# Sheet2.net
KiCad netlist of a schematic drawn in Altium Designer
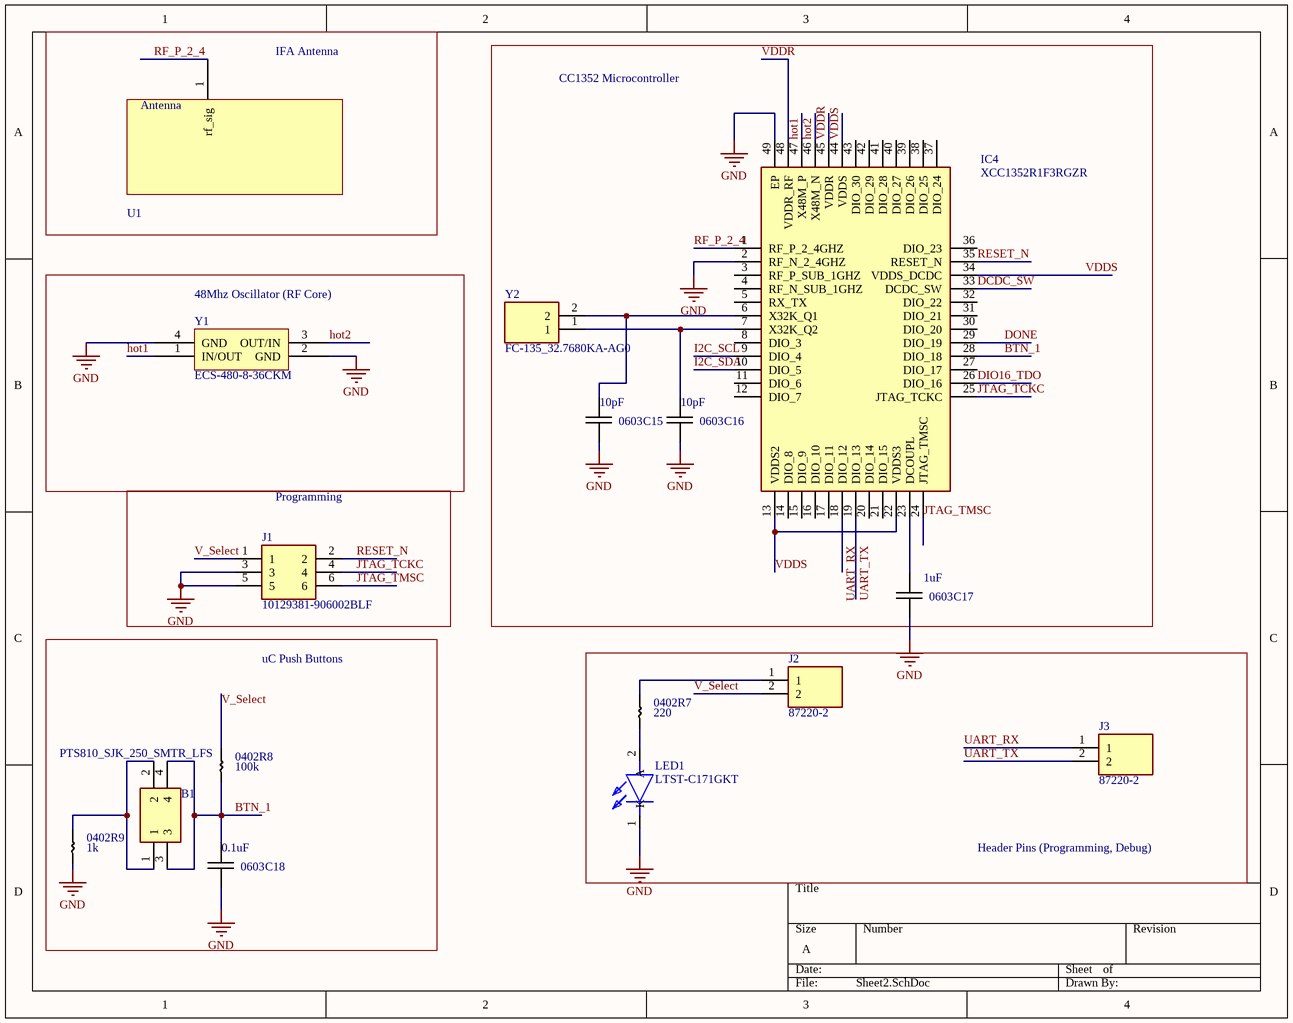
[diagram p0: Sheet2.SchDoc]

(export (version "E")
  (design (tool "Eeschema 10.0.6"))
  (components
    (comp (ref "B1")
      (value "PTS810_SJK_250_SMTR_LFS")
      (footprint "SamacSys:PTS810SJK250SMTRLFS")
      (description "Crystal or Oscillator")
      (fields
        (field (name "MANUFACTURER_PART_NUMBER") "PTS810 SJK 250 SMTR LFS")
        (field (name "MOUSER PART NUMBER") "611-PTS810SJK250SMTR")
      )
      (libsource (lib "*") (part "PTS810_SJK_250_SMTR_LFS"))
    )
    (comp (ref "C15")
      (value "10pF")
      (footprint "0603_SMD")
      (libsource (lib "Enviornmental_Sensor") (part "C_0603"))
    )
    (comp (ref "C16")
      (value "10pF")
      (footprint "0603_SMD")
      (libsource (lib "Enviornmental_Sensor") (part "C_0603"))
    )
    (comp (ref "C17")
      (value "1uF")
      (footprint "0603_SMD")
      (libsource (lib "Enviornmental_Sensor") (part "C_0603"))
    )
    (comp (ref "C18")
      (value "0.1uF")
      (footprint "0603_SMD")
      (libsource (lib "Enviornmental_Sensor") (part "C_0603"))
    )
    (comp (ref "IC4")
      (value "XCC1352R1F3RGZR")
      (footprint "SamacSys:QFN50P700X700X100-49N-D")
      (description "Integrated Circuit")
      (libsource (lib "*") (part "XCC1352R1F3RGZR"))
    )
    (comp (ref "J1")
      (value "10129381-906002BLF")
      (footprint "SamacSys:HDRV6W67P254_2X3_762X483X858P")
      (description "Connector")
      (fields (field (name "MOUSER PART NUMBER") "649-1012938190602BLF"))
      (libsource (lib "*") (part "10129381-906002BLF"))
    )
    (comp (ref "J2")
      (value "87220-2")
      (footprint "SamacSys:HDRV2W67P0X254_1X2_467X234X1083P")
      (description "Connector")
      (fields (field (name "MOUSER PART NUMBER") "571-872202") (field (name "RS PART NUMBER") "7202418P"))
      (libsource (lib "*") (part "87220-2"))
    )
    (comp (ref "J3")
      (value "87220-2")
      (footprint "SamacSys:HDRV2W67P0X254_1X2_467X234X1083P")
      (description "Connector")
      (fields (field (name "MOUSER PART NUMBER") "571-872202") (field (name "RS PART NUMBER") "7202418P"))
      (libsource (lib "*") (part "87220-2"))
    )
    (comp (ref "LED1")
      (value "LTST-C171GKT")
      (footprint "SamacSys:LEDC2012X90N")
      (description "LED")
      (fields
        (field (name "MOUSER PART NUMBER") "859-LTST-C171GKT")
        (field (name "RS PART NUMBER") "6920935P")
      )
      (libsource (lib "*") (part "LTST-C171GKT"))
    )
    (comp (ref "R7")
      (value "220")
      (footprint "0402_SMD")
      (libsource (lib "Enviornmental_Sensor") (part "R_0402"))
    )
    (comp (ref "R8")
      (value "100k")
      (footprint "0402_SMD")
      (libsource (lib "Enviornmental_Sensor") (part "R_0402"))
    )
    (comp (ref "R9")
      (value "1k")
      (footprint "0402_SMD")
      (libsource (lib "Enviornmental_Sensor") (part "R_0402"))
    )
    (comp (ref "U1")
      (value "RF_ANTENNA_2")
      (footprint "RF_TRACE_ANTENNA_2")
      (libsource (lib "V3_Lib") (part "RF_ANTENNA_2"))
    )
    (comp (ref "Y1")
      (value "ECS-480-8-36CKM")
      (footprint "ECS-480-8-36CKM")
      (libsource (lib "Enviornmental_Sensor") (part "ECS-480-8-36CKM"))
    )
    (comp (ref "Y2")
      (value "FC-135_32.7680KA-AG0")
      (footprint "FC135327680KAAG0")
      (description "Crystal or Oscillator")
      (fields
        (field (name "MANUFACTURER_PART_NUMBER") "FC-135 32.7680KA-AG0")
        (field (name "MOUSER PART NUMBER") "732-FC135-32.76KAAG0")
      )
      (libsource (lib "Enviornmental_Sensor") (part "FC-135_32.7680KA-AG0"))
    )
  )
  (nets
    (net (code "1") (name "/BTN_1") (class "Default")
      (node (ref "B1") (pin "3") (pinfunction "3_3") (pintype "passive"))
      (node (ref "B1") (pin "4") (pinfunction "4_4") (pintype "passive"))
      (node (ref "C18") (pin "2") (pinfunction "2_2") (pintype "passive"))
      (node (ref "IC4") (pin "28") (pinfunction "DIO_18_28") (pintype "passive"))
      (node (ref "R8") (pin "2") (pinfunction "2_2") (pintype "passive"))
    )
    (net (code "2") (name "/DCDC_SW") (class "Default")
      (node (ref "IC4") (pin "33") (pinfunction "DCDC_SW_33") (pintype "passive"))
    )
    (net (code "3") (name "/DIO16_TDO") (class "Default")
      (node (ref "IC4") (pin "26") (pinfunction "DIO_16_26") (pintype "passive"))
    )
    (net (code "4") (name "/DONE") (class "Default")
      (node (ref "IC4") (pin "29") (pinfunction "DIO_19_29") (pintype "passive"))
    )
    (net (code "5") (name "/I2C_SCL") (class "Default")
      (node (ref "IC4") (pin "9") (pinfunction "DIO_4_9") (pintype "passive"))
    )
    (net (code "6") (name "/I2C_SDA") (class "Default")
      (node (ref "IC4") (pin "10") (pinfunction "DIO_5_10") (pintype "passive"))
    )
    (net (code "7") (name "/JTAG_TCKC") (class "Default")
      (node (ref "IC4") (pin "25") (pinfunction "JTAG_TCKC_25") (pintype "passive"))
      (node (ref "J1") (pin "4") (pinfunction "4_4") (pintype "passive"))
    )
    (net (code "8") (name "/JTAG_TMSC") (class "Default")
      (node (ref "IC4") (pin "24") (pinfunction "JTAG_TMSC_24") (pintype "passive"))
      (node (ref "J1") (pin "6") (pinfunction "6_6") (pintype "passive"))
    )
    (net (code "9") (name "/RESET_N") (class "Default")
      (node (ref "IC4") (pin "35") (pinfunction "RESET_N_35") (pintype "passive"))
      (node (ref "J1") (pin "2") (pinfunction "2_2") (pintype "passive"))
    )
    (net (code "10") (name "/RF_P_2_4") (class "Default")
      (node (ref "IC4") (pin "1") (pinfunction "RF_P_2_4GHZ_1") (pintype "passive"))
      (node (ref "U1") (pin "1") (pinfunction "rf_sig_1") (pintype "passive"))
    )
    (net (code "11") (name "/UART_RX") (class "Default")
      (node (ref "IC4") (pin "18") (pinfunction "DIO_12_18") (pintype "passive"))
      (node (ref "J3") (pin "1") (pinfunction "1_1") (pintype "passive"))
    )
    (net (code "12") (name "/UART_TX") (class "Default")
      (node (ref "IC4") (pin "19") (pinfunction "DIO_13_19") (pintype "passive"))
      (node (ref "J3") (pin "2") (pinfunction "2_2") (pintype "passive"))
    )
    (net (code "13") (name "/VDDR") (class "Default")
      (node (ref "IC4") (pin "45") (pinfunction "VDDR_45") (pintype "passive"))
      (node (ref "IC4") (pin "48") (pinfunction "VDDR_RF_48") (pintype "passive"))
    )
    (net (code "14") (name "/VDDS") (class "Default")
      (node (ref "IC4") (pin "13") (pinfunction "VDDS2_13") (pintype "passive"))
      (node (ref "IC4") (pin "22") (pinfunction "VDDS3_22") (pintype "passive"))
      (node (ref "IC4") (pin "34") (pinfunction "VDDS_DCDC_34") (pintype "passive"))
      (node (ref "IC4") (pin "44") (pinfunction "VDDS_44") (pintype "passive"))
    )
    (net (code "15") (name "/V_Select") (class "Default")
      (node (ref "J1") (pin "1") (pinfunction "1_1") (pintype "passive"))
      (node (ref "J2") (pin "2") (pinfunction "2_2") (pintype "passive"))
      (node (ref "R8") (pin "1") (pinfunction "1_1") (pintype "passive"))
    )
    (net (code "16") (name "/hot1") (class "Default")
      (node (ref "IC4") (pin "47") (pinfunction "X48M_P_47") (pintype "passive"))
      (node (ref "Y1") (pin "1") (pinfunction "IN/OUT_1") (pintype "passive"))
    )
    (net (code "17") (name "/hot2") (class "Default")
      (node (ref "IC4") (pin "46") (pinfunction "X48M_N_46") (pintype "passive"))
      (node (ref "Y1") (pin "3") (pinfunction "OUT/IN_3") (pintype "passive"))
    )
    (net (code "18") (name "GND") (class "Default")
      (node (ref "C15") (pin "1") (pinfunction "1_1") (pintype "passive"))
      (node (ref "C16") (pin "1") (pinfunction "1_1") (pintype "passive"))
      (node (ref "C17") (pin "1") (pinfunction "1_1") (pintype "passive"))
      (node (ref "C18") (pin "1") (pinfunction "1_1") (pintype "passive"))
      (node (ref "IC4") (pin "2") (pinfunction "RF_N_2_4GHZ_2") (pintype "passive"))
      (node (ref "IC4") (pin "49") (pinfunction "EP_49") (pintype "passive"))
      (node (ref "J1") (pin "3") (pinfunction "3_3") (pintype "passive"))
      (node (ref "J1") (pin "5") (pinfunction "5_5") (pintype "passive"))
      (node (ref "LED1") (pin "1") (pinfunction "K_1") (pintype "passive"))
      (node (ref "R9") (pin "2") (pinfunction "2_2") (pintype "passive"))
      (node (ref "Y1") (pin "2") (pinfunction "GND_2") (pintype "passive"))
      (node (ref "Y1") (pin "4") (pinfunction "GND_4") (pintype "passive"))
    )
    (net (code "19") (name "Net-(B1-Pad1)") (class "Default")
      (node (ref "B1") (pin "1") (pinfunction "1_1") (pintype "passive"))
      (node (ref "B1") (pin "2") (pinfunction "2_2") (pintype "passive"))
      (node (ref "R9") (pin "1") (pinfunction "1_1") (pintype "passive"))
    )
    (net (code "20") (name "Net-(IC4-DCOUPL)") (class "Default")
      (node (ref "C17") (pin "2") (pinfunction "2_2") (pintype "passive"))
      (node (ref "IC4") (pin "23") (pinfunction "DCOUPL_23") (pintype "passive"))
    )
    (net (code "21") (name "Net-(IC4-X32K_Q1)") (class "Default")
      (node (ref "C15") (pin "2") (pinfunction "2_2") (pintype "passive"))
      (node (ref "IC4") (pin "6") (pinfunction "X32K_Q1_6") (pintype "passive"))
      (node (ref "Y2") (pin "2") (pinfunction "2_2") (pintype "passive"))
    )
    (net (code "22") (name "Net-(IC4-X32K_Q2)") (class "Default")
      (node (ref "C16") (pin "2") (pinfunction "2_2") (pintype "passive"))
      (node (ref "IC4") (pin "7") (pinfunction "X32K_Q2_7") (pintype "passive"))
      (node (ref "Y2") (pin "1") (pinfunction "1_1") (pintype "passive"))
    )
    (net (code "23") (name "Net-(J2-Pad1)") (class "Default")
      (node (ref "J2") (pin "1") (pinfunction "1_1") (pintype "passive"))
      (node (ref "R7") (pin "1") (pinfunction "1_1") (pintype "passive"))
    )
    (net (code "24") (name "Net-(LED1-A)") (class "Default")
      (node (ref "LED1") (pin "2") (pinfunction "A_2") (pintype "passive"))
      (node (ref "R7") (pin "2") (pinfunction "2_2") (pintype "passive"))
    )
    (net (code "25") (name "unconnected-(IC4-DIO_3-Pad8)") (class "Default")
      (node (ref "IC4") (pin "8") (pinfunction "DIO_3_8") (pintype "passive"))
    )
    (net (code "26") (name "unconnected-(IC4-DIO_6-Pad11)") (class "Default")
      (node (ref "IC4") (pin "11") (pinfunction "DIO_6_11") (pintype "passive"))
    )
    (net (code "27") (name "unconnected-(IC4-DIO_7-Pad12)") (class "Default")
      (node (ref "IC4") (pin "12") (pinfunction "DIO_7_12") (pintype "passive"))
    )
    (net (code "28") (name "unconnected-(IC4-DIO_8-Pad14)") (class "Default")
      (node (ref "IC4") (pin "14") (pinfunction "DIO_8_14") (pintype "passive"))
    )
    (net (code "29") (name "unconnected-(IC4-DIO_9-Pad15)") (class "Default")
      (node (ref "IC4") (pin "15") (pinfunction "DIO_9_15") (pintype "passive"))
    )
    (net (code "30") (name "unconnected-(IC4-DIO_10-Pad16)") (class "Default")
      (node (ref "IC4") (pin "16") (pinfunction "DIO_10_16") (pintype "passive"))
    )
    (net (code "31") (name "unconnected-(IC4-DIO_11-Pad17)") (class "Default")
      (node (ref "IC4") (pin "17") (pinfunction "DIO_11_17") (pintype "passive"))
    )
    (net (code "32") (name "unconnected-(IC4-DIO_14-Pad20)") (class "Default")
      (node (ref "IC4") (pin "20") (pinfunction "DIO_14_20") (pintype "passive"))
    )
    (net (code "33") (name "unconnected-(IC4-DIO_15-Pad21)") (class "Default")
      (node (ref "IC4") (pin "21") (pinfunction "DIO_15_21") (pintype "passive"))
    )
    (net (code "34") (name "unconnected-(IC4-DIO_17-Pad27)") (class "Default")
      (node (ref "IC4") (pin "27") (pinfunction "DIO_17_27") (pintype "passive"))
    )
    (net (code "35") (name "unconnected-(IC4-DIO_20-Pad30)") (class "Default")
      (node (ref "IC4") (pin "30") (pinfunction "DIO_20_30") (pintype "passive"))
    )
    (net (code "36") (name "unconnected-(IC4-DIO_21-Pad31)") (class "Default")
      (node (ref "IC4") (pin "31") (pinfunction "DIO_21_31") (pintype "passive"))
    )
    (net (code "37") (name "unconnected-(IC4-DIO_22-Pad32)") (class "Default")
      (node (ref "IC4") (pin "32") (pinfunction "DIO_22_32") (pintype "passive"))
    )
    (net (code "38") (name "unconnected-(IC4-DIO_23-Pad36)") (class "Default")
      (node (ref "IC4") (pin "36") (pinfunction "DIO_23_36") (pintype "passive"))
    )
    (net (code "39") (name "unconnected-(IC4-DIO_24-Pad37)") (class "Default")
      (node (ref "IC4") (pin "37") (pinfunction "DIO_24_37") (pintype "passive"))
    )
    (net (code "40") (name "unconnected-(IC4-DIO_25-Pad38)") (class "Default")
      (node (ref "IC4") (pin "38") (pinfunction "DIO_25_38") (pintype "passive"))
    )
    (net (code "41") (name "unconnected-(IC4-DIO_26-Pad39)") (class "Default")
      (node (ref "IC4") (pin "39") (pinfunction "DIO_26_39") (pintype "passive"))
    )
    (net (code "42") (name "unconnected-(IC4-DIO_27-Pad40)") (class "Default")
      (node (ref "IC4") (pin "40") (pinfunction "DIO_27_40") (pintype "passive"))
    )
    (net (code "43") (name "unconnected-(IC4-DIO_28-Pad41)") (class "Default")
      (node (ref "IC4") (pin "41") (pinfunction "DIO_28_41") (pintype "passive"))
    )
    (net (code "44") (name "unconnected-(IC4-DIO_29-Pad42)") (class "Default")
      (node (ref "IC4") (pin "42") (pinfunction "DIO_29_42") (pintype "passive"))
    )
    (net (code "45") (name "unconnected-(IC4-DIO_30-Pad43)") (class "Default")
      (node (ref "IC4") (pin "43") (pinfunction "DIO_30_43") (pintype "passive"))
    )
    (net (code "46") (name "unconnected-(IC4-RF_N_SUB_1GHZ-Pad4)") (class "Default")
      (node (ref "IC4") (pin "4") (pinfunction "RF_N_SUB_1GHZ_4") (pintype "passive"))
    )
    (net (code "47") (name "unconnected-(IC4-RF_P_SUB_1GHZ-Pad3)") (class "Default")
      (node (ref "IC4") (pin "3") (pinfunction "RF_P_SUB_1GHZ_3") (pintype "passive"))
    )
    (net (code "48") (name "unconnected-(IC4-RX_TX-Pad5)") (class "Default")
      (node (ref "IC4") (pin "5") (pinfunction "RX_TX_5") (pintype "passive"))
    )
  )
)
